# ASD2413.net
KiCad netlist of a schematic drawn in EAGLE
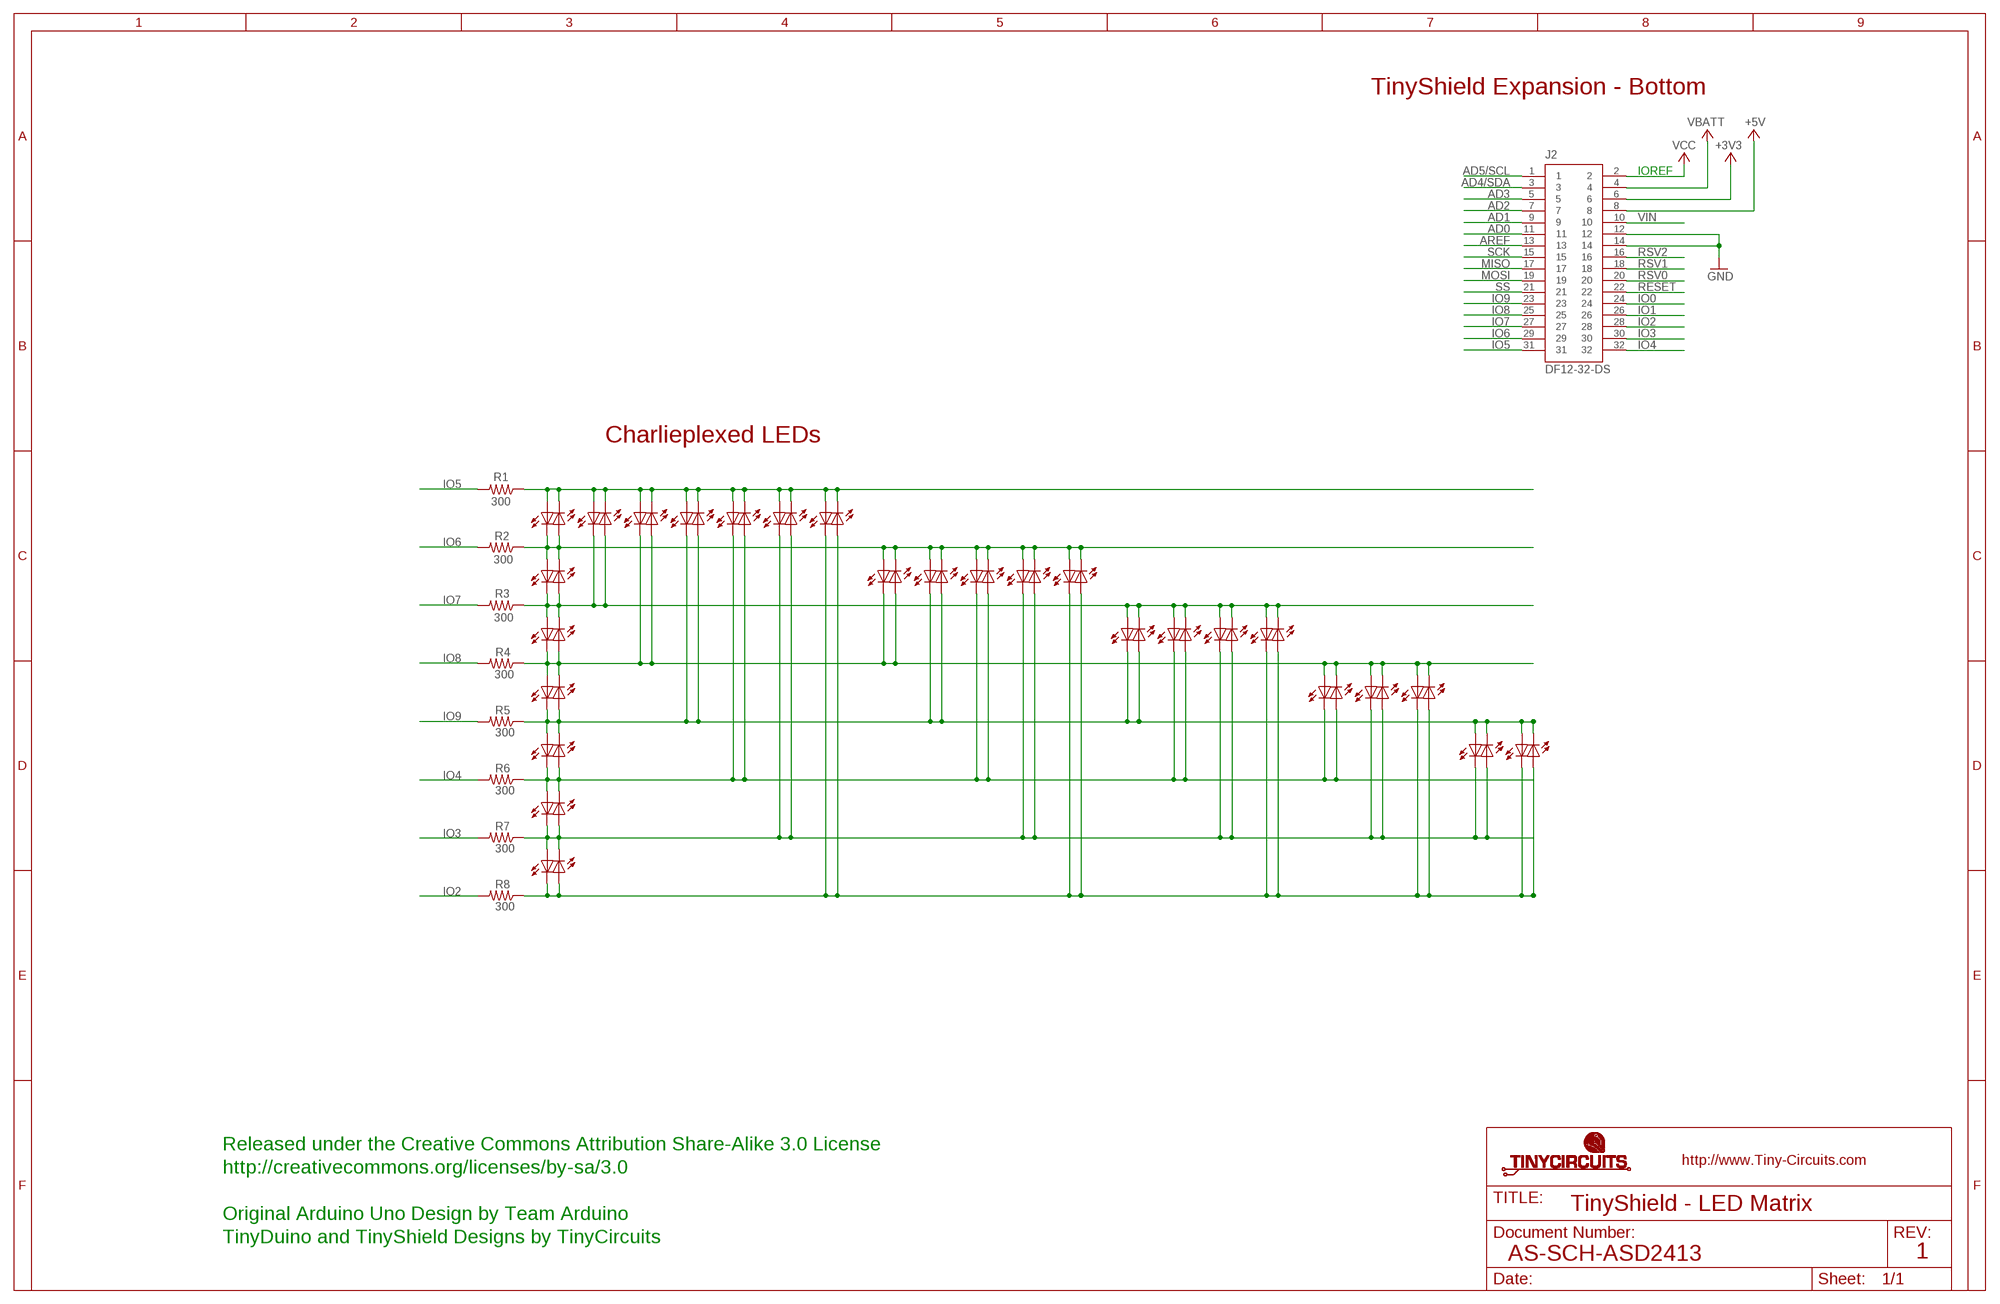
[diagram p0: schematic, sheet 1]

(export (version "E")
  (design (tool "Eeschema 10.0.6"))
  (components
    (comp (ref "D17")
      (value "GREEN")
      (footprint "eagle-import:0402_LED")
      (fields (field (name "PARTNO") "AS-ITM-00038") (field (name "PARTNO_1") "AS-ITM-00038"))
      (libsource (lib "eagle-import") (part "AS-ITM-00038"))
    )
    (comp (ref "D18")
      (value "GREEN")
      (footprint "eagle-import:0402_LED")
      (fields (field (name "PARTNO") "AS-ITM-00038") (field (name "PARTNO_1") "AS-ITM-00038"))
      (libsource (lib "eagle-import") (part "AS-ITM-00038"))
    )
    (comp (ref "D19")
      (value "GREEN")
      (footprint "eagle-import:0402_LED")
      (fields (field (name "PARTNO") "AS-ITM-00038") (field (name "PARTNO_1") "AS-ITM-00038"))
      (libsource (lib "eagle-import") (part "AS-ITM-00038"))
    )
    (comp (ref "D20")
      (value "GREEN")
      (footprint "eagle-import:0402_LED")
      (fields (field (name "PARTNO") "AS-ITM-00038") (field (name "PARTNO_1") "AS-ITM-00038"))
      (libsource (lib "eagle-import") (part "AS-ITM-00038"))
    )
    (comp (ref "D21")
      (value "GREEN")
      (footprint "eagle-import:0402_LED")
      (fields (field (name "PARTNO") "AS-ITM-00038") (field (name "PARTNO_1") "AS-ITM-00038"))
      (libsource (lib "eagle-import") (part "AS-ITM-00038"))
    )
    (comp (ref "D22")
      (value "GREEN")
      (footprint "eagle-import:0402_LED")
      (fields (field (name "PARTNO") "AS-ITM-00038") (field (name "PARTNO_1") "AS-ITM-00038"))
      (libsource (lib "eagle-import") (part "AS-ITM-00038"))
    )
    (comp (ref "D53")
      (value "GREEN")
      (footprint "eagle-import:0402_LED")
      (fields (field (name "PARTNO") "AS-ITM-00038") (field (name "PARTNO_1") "AS-ITM-00038"))
      (libsource (lib "eagle-import") (part "AS-ITM-00038"))
    )
    (comp (ref "D54")
      (value "GREEN")
      (footprint "eagle-import:0402_LED")
      (fields (field (name "PARTNO") "AS-ITM-00038") (field (name "PARTNO_1") "AS-ITM-00038"))
      (libsource (lib "eagle-import") (part "AS-ITM-00038"))
    )
    (comp (ref "D55")
      (value "GREEN")
      (footprint "eagle-import:0402_LED")
      (fields (field (name "PARTNO") "AS-ITM-00038") (field (name "PARTNO_1") "AS-ITM-00038"))
      (libsource (lib "eagle-import") (part "AS-ITM-00038"))
    )
    (comp (ref "D56")
      (value "GREEN")
      (footprint "eagle-import:0402_LED")
      (fields (field (name "PARTNO") "AS-ITM-00038") (field (name "PARTNO_1") "AS-ITM-00038"))
      (libsource (lib "eagle-import") (part "AS-ITM-00038"))
    )
    (comp (ref "D57")
      (value "GREEN")
      (footprint "eagle-import:0402_LED")
      (fields (field (name "PARTNO") "AS-ITM-00038") (field (name "PARTNO_1") "AS-ITM-00038"))
      (libsource (lib "eagle-import") (part "AS-ITM-00038"))
    )
    (comp (ref "D58")
      (value "GREEN")
      (footprint "eagle-import:0402_LED")
      (fields (field (name "PARTNO") "AS-ITM-00038") (field (name "PARTNO_1") "AS-ITM-00038"))
      (libsource (lib "eagle-import") (part "AS-ITM-00038"))
    )
    (comp (ref "D59")
      (value "GREEN")
      (footprint "eagle-import:0402_LED")
      (fields (field (name "PARTNO") "AS-ITM-00038") (field (name "PARTNO_1") "AS-ITM-00038"))
      (libsource (lib "eagle-import") (part "AS-ITM-00038"))
    )
    (comp (ref "D60")
      (value "GREEN")
      (footprint "eagle-import:0402_LED")
      (fields (field (name "PARTNO") "AS-ITM-00038") (field (name "PARTNO_1") "AS-ITM-00038"))
      (libsource (lib "eagle-import") (part "AS-ITM-00038"))
    )
    (comp (ref "D61")
      (value "GREEN")
      (footprint "eagle-import:0402_LED")
      (fields (field (name "PARTNO") "AS-ITM-00038") (field (name "PARTNO_1") "AS-ITM-00038"))
      (libsource (lib "eagle-import") (part "AS-ITM-00038"))
    )
    (comp (ref "D62")
      (value "GREEN")
      (footprint "eagle-import:0402_LED")
      (fields (field (name "PARTNO") "AS-ITM-00038") (field (name "PARTNO_1") "AS-ITM-00038"))
      (libsource (lib "eagle-import") (part "AS-ITM-00038"))
    )
    (comp (ref "D63")
      (value "GREEN")
      (footprint "eagle-import:0402_LED")
      (fields (field (name "PARTNO") "AS-ITM-00038") (field (name "PARTNO_1") "AS-ITM-00038"))
      (libsource (lib "eagle-import") (part "AS-ITM-00038"))
    )
    (comp (ref "D64")
      (value "GREEN")
      (footprint "eagle-import:0402_LED")
      (fields (field (name "PARTNO") "AS-ITM-00038") (field (name "PARTNO_1") "AS-ITM-00038"))
      (libsource (lib "eagle-import") (part "AS-ITM-00038"))
    )
    (comp (ref "D65")
      (value "GREEN")
      (footprint "eagle-import:0402_LED")
      (fields (field (name "PARTNO") "AS-ITM-00038") (field (name "PARTNO_1") "AS-ITM-00038"))
      (libsource (lib "eagle-import") (part "AS-ITM-00038"))
    )
    (comp (ref "D66")
      (value "GREEN")
      (footprint "eagle-import:0402_LED")
      (fields (field (name "PARTNO") "AS-ITM-00038") (field (name "PARTNO_1") "AS-ITM-00038"))
      (libsource (lib "eagle-import") (part "AS-ITM-00038"))
    )
    (comp (ref "D67")
      (value "GREEN")
      (footprint "eagle-import:0402_LED")
      (fields (field (name "PARTNO") "AS-ITM-00038") (field (name "PARTNO_1") "AS-ITM-00038"))
      (libsource (lib "eagle-import") (part "AS-ITM-00038"))
    )
    (comp (ref "D68")
      (value "GREEN")
      (footprint "eagle-import:0402_LED")
      (fields (field (name "PARTNO") "AS-ITM-00038") (field (name "PARTNO_1") "AS-ITM-00038"))
      (libsource (lib "eagle-import") (part "AS-ITM-00038"))
    )
    (comp (ref "D69")
      (value "GREEN")
      (footprint "eagle-import:0402_LED")
      (fields (field (name "PARTNO") "AS-ITM-00038") (field (name "PARTNO_1") "AS-ITM-00038"))
      (libsource (lib "eagle-import") (part "AS-ITM-00038"))
    )
    (comp (ref "D70")
      (value "GREEN")
      (footprint "eagle-import:0402_LED")
      (fields (field (name "PARTNO") "AS-ITM-00038") (field (name "PARTNO_1") "AS-ITM-00038"))
      (libsource (lib "eagle-import") (part "AS-ITM-00038"))
    )
    (comp (ref "D71")
      (value "GREEN")
      (footprint "eagle-import:0402_LED")
      (fields (field (name "PARTNO") "AS-ITM-00038") (field (name "PARTNO_1") "AS-ITM-00038"))
      (libsource (lib "eagle-import") (part "AS-ITM-00038"))
    )
    (comp (ref "D72")
      (value "GREEN")
      (footprint "eagle-import:0402_LED")
      (fields (field (name "PARTNO") "AS-ITM-00038") (field (name "PARTNO_1") "AS-ITM-00038"))
      (libsource (lib "eagle-import") (part "AS-ITM-00038"))
    )
    (comp (ref "D73")
      (value "GREEN")
      (footprint "eagle-import:0402_LED")
      (fields (field (name "PARTNO") "AS-ITM-00038") (field (name "PARTNO_1") "AS-ITM-00038"))
      (libsource (lib "eagle-import") (part "AS-ITM-00038"))
    )
    (comp (ref "D74")
      (value "GREEN")
      (footprint "eagle-import:0402_LED")
      (fields (field (name "PARTNO") "AS-ITM-00038") (field (name "PARTNO_1") "AS-ITM-00038"))
      (libsource (lib "eagle-import") (part "AS-ITM-00038"))
    )
    (comp (ref "D75")
      (value "GREEN")
      (footprint "eagle-import:0402_LED")
      (fields (field (name "PARTNO") "AS-ITM-00038") (field (name "PARTNO_1") "AS-ITM-00038"))
      (libsource (lib "eagle-import") (part "AS-ITM-00038"))
    )
    (comp (ref "D76")
      (value "GREEN")
      (footprint "eagle-import:0402_LED")
      (fields (field (name "PARTNO") "AS-ITM-00038") (field (name "PARTNO_1") "AS-ITM-00038"))
      (libsource (lib "eagle-import") (part "AS-ITM-00038"))
    )
    (comp (ref "D77")
      (value "GREEN")
      (footprint "eagle-import:0402_LED")
      (fields (field (name "PARTNO") "AS-ITM-00038") (field (name "PARTNO_1") "AS-ITM-00038"))
      (libsource (lib "eagle-import") (part "AS-ITM-00038"))
    )
    (comp (ref "D78")
      (value "GREEN")
      (footprint "eagle-import:0402_LED")
      (fields (field (name "PARTNO") "AS-ITM-00038") (field (name "PARTNO_1") "AS-ITM-00038"))
      (libsource (lib "eagle-import") (part "AS-ITM-00038"))
    )
    (comp (ref "D79")
      (value "GREEN")
      (footprint "eagle-import:0402_LED")
      (fields (field (name "PARTNO") "AS-ITM-00038") (field (name "PARTNO_1") "AS-ITM-00038"))
      (libsource (lib "eagle-import") (part "AS-ITM-00038"))
    )
    (comp (ref "D80")
      (value "GREEN")
      (footprint "eagle-import:0402_LED")
      (fields (field (name "PARTNO") "AS-ITM-00038") (field (name "PARTNO_1") "AS-ITM-00038"))
      (libsource (lib "eagle-import") (part "AS-ITM-00038"))
    )
    (comp (ref "D81")
      (value "GREEN")
      (footprint "eagle-import:0402_LED")
      (fields (field (name "PARTNO") "AS-ITM-00038") (field (name "PARTNO_1") "AS-ITM-00038"))
      (libsource (lib "eagle-import") (part "AS-ITM-00038"))
    )
    (comp (ref "D82")
      (value "GREEN")
      (footprint "eagle-import:0402_LED")
      (fields (field (name "PARTNO") "AS-ITM-00038") (field (name "PARTNO_1") "AS-ITM-00038"))
      (libsource (lib "eagle-import") (part "AS-ITM-00038"))
    )
    (comp (ref "D83")
      (value "GREEN")
      (footprint "eagle-import:0402_LED")
      (fields (field (name "PARTNO") "AS-ITM-00038") (field (name "PARTNO_1") "AS-ITM-00038"))
      (libsource (lib "eagle-import") (part "AS-ITM-00038"))
    )
    (comp (ref "D84")
      (value "GREEN")
      (footprint "eagle-import:0402_LED")
      (fields (field (name "PARTNO") "AS-ITM-00038") (field (name "PARTNO_1") "AS-ITM-00038"))
      (libsource (lib "eagle-import") (part "AS-ITM-00038"))
    )
    (comp (ref "D85")
      (value "GREEN")
      (footprint "eagle-import:0402_LED")
      (fields (field (name "PARTNO") "AS-ITM-00038") (field (name "PARTNO_1") "AS-ITM-00038"))
      (libsource (lib "eagle-import") (part "AS-ITM-00038"))
    )
    (comp (ref "D86")
      (value "GREEN")
      (footprint "eagle-import:0402_LED")
      (fields (field (name "PARTNO") "AS-ITM-00038") (field (name "PARTNO_1") "AS-ITM-00038"))
      (libsource (lib "eagle-import") (part "AS-ITM-00038"))
    )
    (comp (ref "D87")
      (value "GREEN")
      (footprint "eagle-import:0402_LED")
      (fields (field (name "PARTNO") "AS-ITM-00038") (field (name "PARTNO_1") "AS-ITM-00038"))
      (libsource (lib "eagle-import") (part "AS-ITM-00038"))
    )
    (comp (ref "D88")
      (value "GREEN")
      (footprint "eagle-import:0402_LED")
      (fields (field (name "PARTNO") "AS-ITM-00038") (field (name "PARTNO_1") "AS-ITM-00038"))
      (libsource (lib "eagle-import") (part "AS-ITM-00038"))
    )
    (comp (ref "D89")
      (value "GREEN")
      (footprint "eagle-import:0402_LED")
      (fields (field (name "PARTNO") "AS-ITM-00038") (field (name "PARTNO_1") "AS-ITM-00038"))
      (libsource (lib "eagle-import") (part "AS-ITM-00038"))
    )
    (comp (ref "D90")
      (value "GREEN")
      (footprint "eagle-import:0402_LED")
      (fields (field (name "PARTNO") "AS-ITM-00038") (field (name "PARTNO_1") "AS-ITM-00038"))
      (libsource (lib "eagle-import") (part "AS-ITM-00038"))
    )
    (comp (ref "D91")
      (value "GREEN")
      (footprint "eagle-import:0402_LED")
      (fields (field (name "PARTNO") "AS-ITM-00038") (field (name "PARTNO_1") "AS-ITM-00038"))
      (libsource (lib "eagle-import") (part "AS-ITM-00038"))
    )
    (comp (ref "D92")
      (value "GREEN")
      (footprint "eagle-import:0402_LED")
      (fields (field (name "PARTNO") "AS-ITM-00038") (field (name "PARTNO_1") "AS-ITM-00038"))
      (libsource (lib "eagle-import") (part "AS-ITM-00038"))
    )
    (comp (ref "D93")
      (value "GREEN")
      (footprint "eagle-import:0402_LED")
      (fields (field (name "PARTNO") "AS-ITM-00038") (field (name "PARTNO_1") "AS-ITM-00038"))
      (libsource (lib "eagle-import") (part "AS-ITM-00038"))
    )
    (comp (ref "D94")
      (value "GREEN")
      (footprint "eagle-import:0402_LED")
      (fields (field (name "PARTNO") "AS-ITM-00038") (field (name "PARTNO_1") "AS-ITM-00038"))
      (libsource (lib "eagle-import") (part "AS-ITM-00038"))
    )
    (comp (ref "D95")
      (value "GREEN")
      (footprint "eagle-import:0402_LED")
      (fields (field (name "PARTNO") "AS-ITM-00038") (field (name "PARTNO_1") "AS-ITM-00038"))
      (libsource (lib "eagle-import") (part "AS-ITM-00038"))
    )
    (comp (ref "D96")
      (value "GREEN")
      (footprint "eagle-import:0402_LED")
      (fields (field (name "PARTNO") "AS-ITM-00038") (field (name "PARTNO_1") "AS-ITM-00038"))
      (libsource (lib "eagle-import") (part "AS-ITM-00038"))
    )
    (comp (ref "D97")
      (value "GREEN")
      (footprint "eagle-import:0402_LED")
      (fields (field (name "PARTNO") "AS-ITM-00038") (field (name "PARTNO_1") "AS-ITM-00038"))
      (libsource (lib "eagle-import") (part "AS-ITM-00038"))
    )
    (comp (ref "D98")
      (value "GREEN")
      (footprint "eagle-import:0402_LED")
      (fields (field (name "PARTNO") "AS-ITM-00038") (field (name "PARTNO_1") "AS-ITM-00038"))
      (libsource (lib "eagle-import") (part "AS-ITM-00038"))
    )
    (comp (ref "D99")
      (value "GREEN")
      (footprint "eagle-import:0402_LED")
      (fields (field (name "PARTNO") "AS-ITM-00038") (field (name "PARTNO_1") "AS-ITM-00038"))
      (libsource (lib "eagle-import") (part "AS-ITM-00038"))
    )
    (comp (ref "D100")
      (value "GREEN")
      (footprint "eagle-import:0402_LED")
      (fields (field (name "PARTNO") "AS-ITM-00038") (field (name "PARTNO_1") "AS-ITM-00038"))
      (libsource (lib "eagle-import") (part "AS-ITM-00038"))
    )
    (comp (ref "J2")
      (value "DF12-32-DS")
      (footprint "eagle-import:DF12-32-DS")
      (fields (field (name "PARTNO") "AS-ITM-00012") (field (name "PARTNO_1") "AS-ITM-00012"))
      (libsource (lib "eagle-import") (part "AS-ITM-00012"))
    )
    (comp (ref "R1")
      (value "300")
      (footprint "eagle-import:0402")
      (fields (field (name "PARTNO") "AS-ITM-00016") (field (name "PARTNO_1") "AS-ITM-00016"))
      (libsource (lib "eagle-import") (part "AS-ITM-00016"))
    )
    (comp (ref "R2")
      (value "300")
      (footprint "eagle-import:0402")
      (fields (field (name "PARTNO") "AS-ITM-00016"))
      (libsource (lib "eagle-import") (part "AS-ITM-00016"))
    )
    (comp (ref "R3")
      (value "300")
      (footprint "eagle-import:0402")
      (fields (field (name "PARTNO") "AS-ITM-00016"))
      (libsource (lib "eagle-import") (part "AS-ITM-00016"))
    )
    (comp (ref "R4")
      (value "300")
      (footprint "eagle-import:0402")
      (fields (field (name "PARTNO") "AS-ITM-00016"))
      (libsource (lib "eagle-import") (part "AS-ITM-00016"))
    )
    (comp (ref "R5")
      (value "300")
      (footprint "eagle-import:0402")
      (fields (field (name "PARTNO") "AS-ITM-00016"))
      (libsource (lib "eagle-import") (part "AS-ITM-00016"))
    )
    (comp (ref "R6")
      (value "300")
      (footprint "eagle-import:0402")
      (fields (field (name "PARTNO") "AS-ITM-00016") (field (name "PARTNO_1") "AS-ITM-00016"))
      (libsource (lib "eagle-import") (part "AS-ITM-00016"))
    )
    (comp (ref "R7")
      (value "300")
      (footprint "eagle-import:0402")
      (fields (field (name "PARTNO") "AS-ITM-00016") (field (name "PARTNO_1") "AS-ITM-00016"))
      (libsource (lib "eagle-import") (part "AS-ITM-00016"))
    )
    (comp (ref "R8")
      (value "300")
      (footprint "eagle-import:0402")
      (fields (field (name "PARTNO") "AS-ITM-00016") (field (name "PARTNO_1") "AS-ITM-00016"))
      (libsource (lib "eagle-import") (part "AS-ITM-00016"))
    )
  )
  (nets
    (net (code "1") (name "+3V3") (class "Default")
      (node (ref "J2") (pin "6") (pinfunction "6_6") (pintype "bidirectional"))
    )
    (net (code "2") (name "+5V") (class "Default")
      (node (ref "J2") (pin "8") (pinfunction "8_8") (pintype "bidirectional"))
    )
    (net (code "3") (name "/AD0") (class "Default")
      (node (ref "J2") (pin "11") (pinfunction "11_11") (pintype "bidirectional"))
    )
    (net (code "4") (name "/AD1") (class "Default")
      (node (ref "J2") (pin "9") (pinfunction "9_9") (pintype "bidirectional"))
    )
    (net (code "5") (name "/AD2") (class "Default")
      (node (ref "J2") (pin "7") (pinfunction "7_7") (pintype "bidirectional"))
    )
    (net (code "6") (name "/AD3") (class "Default")
      (node (ref "J2") (pin "5") (pinfunction "5_5") (pintype "bidirectional"))
    )
    (net (code "7") (name "/AD4{slash}SDA") (class "Default")
      (node (ref "J2") (pin "3") (pinfunction "3_3") (pintype "bidirectional"))
    )
    (net (code "8") (name "/AD5{slash}SCL") (class "Default")
      (node (ref "J2") (pin "1") (pinfunction "1_1") (pintype "bidirectional"))
    )
    (net (code "9") (name "/AREF") (class "Default")
      (node (ref "J2") (pin "13") (pinfunction "13_13") (pintype "bidirectional"))
    )
    (net (code "10") (name "/IO0") (class "Default")
      (node (ref "J2") (pin "24") (pinfunction "24_24") (pintype "bidirectional"))
    )
    (net (code "11") (name "/IO1") (class "Default")
      (node (ref "J2") (pin "26") (pinfunction "26_26") (pintype "bidirectional"))
    )
    (net (code "12") (name "/IO2") (class "Default")
      (node (ref "J2") (pin "28") (pinfunction "28_28") (pintype "bidirectional"))
      (node (ref "R8") (pin "2") (pinfunction "2_2") (pintype "passive"))
    )
    (net (code "13") (name "/IO3") (class "Default")
      (node (ref "J2") (pin "30") (pinfunction "30_30") (pintype "bidirectional"))
      (node (ref "R7") (pin "2") (pinfunction "2_2") (pintype "passive"))
    )
    (net (code "14") (name "/IO4") (class "Default")
      (node (ref "J2") (pin "32") (pinfunction "32_32") (pintype "bidirectional"))
      (node (ref "R6") (pin "2") (pinfunction "2_2") (pintype "passive"))
    )
    (net (code "15") (name "/IO5") (class "Default")
      (node (ref "J2") (pin "31") (pinfunction "31_31") (pintype "bidirectional"))
      (node (ref "R1") (pin "2") (pinfunction "2_2") (pintype "passive"))
    )
    (net (code "16") (name "/IO6") (class "Default")
      (node (ref "J2") (pin "29") (pinfunction "29_29") (pintype "bidirectional"))
      (node (ref "R2") (pin "2") (pinfunction "2_2") (pintype "passive"))
    )
    (net (code "17") (name "/IO7") (class "Default")
      (node (ref "J2") (pin "27") (pinfunction "27_27") (pintype "bidirectional"))
      (node (ref "R3") (pin "2") (pinfunction "2_2") (pintype "passive"))
    )
    (net (code "18") (name "/IO8") (class "Default")
      (node (ref "J2") (pin "25") (pinfunction "25_25") (pintype "bidirectional"))
      (node (ref "R4") (pin "2") (pinfunction "2_2") (pintype "passive"))
    )
    (net (code "19") (name "/IO9") (class "Default")
      (node (ref "J2") (pin "23") (pinfunction "23_23") (pintype "bidirectional"))
      (node (ref "R5") (pin "2") (pinfunction "2_2") (pintype "passive"))
    )
    (net (code "20") (name "/MISO") (class "Default")
      (node (ref "J2") (pin "17") (pinfunction "17_17") (pintype "bidirectional"))
    )
    (net (code "21") (name "/MOSI") (class "Default")
      (node (ref "J2") (pin "19") (pinfunction "19_19") (pintype "bidirectional"))
    )
    (net (code "22") (name "/RESET") (class "Default")
      (node (ref "J2") (pin "22") (pinfunction "22_22") (pintype "bidirectional"))
    )
    (net (code "23") (name "/RSV0") (class "Default")
      (node (ref "J2") (pin "20") (pinfunction "20_20") (pintype "bidirectional"))
    )
    (net (code "24") (name "/RSV1") (class "Default")
      (node (ref "J2") (pin "18") (pinfunction "18_18") (pintype "bidirectional"))
    )
    (net (code "25") (name "/RSV2") (class "Default")
      (node (ref "J2") (pin "16") (pinfunction "16_16") (pintype "bidirectional"))
    )
    (net (code "26") (name "/SCK") (class "Default")
      (node (ref "J2") (pin "15") (pinfunction "15_15") (pintype "bidirectional"))
    )
    (net (code "27") (name "/SS") (class "Default")
      (node (ref "J2") (pin "21") (pinfunction "21_21") (pintype "bidirectional"))
    )
    (net (code "28") (name "/VIN") (class "Default")
      (node (ref "J2") (pin "10") (pinfunction "10_10") (pintype "bidirectional"))
    )
    (net (code "29") (name "GND") (class "Default")
      (node (ref "J2") (pin "12") (pinfunction "12_12") (pintype "bidirectional"))
      (node (ref "J2") (pin "14") (pinfunction "14_14") (pintype "bidirectional"))
    )
    (net (code "30") (name "Net-(D17-A)") (class "Default")
      (node (ref "D17") (pin "1") (pinfunction "A_1") (pintype "passive"))
      (node (ref "D18") (pin "2") (pinfunction "C_2") (pintype "passive"))
      (node (ref "D19") (pin "1") (pinfunction "A_1") (pintype "passive"))
      (node (ref "D20") (pin "2") (pinfunction "C_2") (pintype "passive"))
      (node (ref "D21") (pin "1") (pinfunction "A_1") (pintype "passive"))
      (node (ref "D22") (pin "2") (pinfunction "C_2") (pintype "passive"))
      (node (ref "D53") (pin "1") (pinfunction "A_1") (pintype "passive"))
      (node (ref "D54") (pin "2") (pinfunction "C_2") (pintype "passive"))
      (node (ref "D55") (pin "1") (pinfunction "A_1") (pintype "passive"))
      (node (ref "D56") (pin "2") (pinfunction "C_2") (pintype "passive"))
      (node (ref "D57") (pin "1") (pinfunction "A_1") (pintype "passive"))
      (node (ref "D58") (pin "2") (pinfunction "C_2") (pintype "passive"))
      (node (ref "D59") (pin "1") (pinfunction "A_1") (pintype "passive"))
      (node (ref "D60") (pin "2") (pinfunction "C_2") (pintype "passive"))
      (node (ref "R1") (pin "1") (pinfunction "1_1") (pintype "passive"))
    )
    (net (code "31") (name "Net-(D17-C)") (class "Default")
      (node (ref "D17") (pin "2") (pinfunction "C_2") (pintype "passive"))
      (node (ref "D18") (pin "1") (pinfunction "A_1") (pintype "passive"))
      (node (ref "D61") (pin "1") (pinfunction "A_1") (pintype "passive"))
      (node (ref "D62") (pin "2") (pinfunction "C_2") (pintype "passive"))
      (node (ref "D63") (pin "1") (pinfunction "A_1") (pintype "passive"))
      (node (ref "D64") (pin "2") (pinfunction "C_2") (pintype "passive"))
      (node (ref "D65") (pin "1") (pinfunction "A_1") (pintype "passive"))
      (node (ref "D66") (pin "2") (pinfunction "C_2") (pintype "passive"))
      (node (ref "D67") (pin "1") (pinfunction "A_1") (pintype "passive"))
      (node (ref "D68") (pin "2") (pinfunction "C_2") (pintype "passive"))
      (node (ref "D69") (pin "1") (pinfunction "A_1") (pintype "passive"))
      (node (ref "D70") (pin "2") (pinfunction "C_2") (pintype "passive"))
      (node (ref "D85") (pin "1") (pinfunction "A_1") (pintype "passive"))
      (node (ref "D86") (pin "2") (pinfunction "C_2") (pintype "passive"))
      (node (ref "R2") (pin "1") (pinfunction "1_1") (pintype "passive"))
    )
    (net (code "32") (name "Net-(D19-C)") (class "Default")
      (node (ref "D19") (pin "2") (pinfunction "C_2") (pintype "passive"))
      (node (ref "D20") (pin "1") (pinfunction "A_1") (pintype "passive"))
      (node (ref "D61") (pin "2") (pinfunction "C_2") (pintype "passive"))
      (node (ref "D62") (pin "1") (pinfunction "A_1") (pintype "passive"))
      (node (ref "D71") (pin "1") (pinfunction "A_1") (pintype "passive"))
      (node (ref "D72") (pin "2") (pinfunction "C_2") (pintype "passive"))
      (node (ref "D73") (pin "1") (pinfunction "A_1") (pintype "passive"))
      (node (ref "D74") (pin "2") (pinfunction "C_2") (pintype "passive"))
      (node (ref "D83") (pin "1") (pinfunction "A_1") (pintype "passive"))
      (node (ref "D84") (pin "2") (pinfunction "C_2") (pintype "passive"))
      (node (ref "D87") (pin "1") (pinfunction "A_1") (pintype "passive"))
      (node (ref "D88") (pin "2") (pinfunction "C_2") (pintype "passive"))
      (node (ref "D89") (pin "1") (pinfunction "A_1") (pintype "passive"))
      (node (ref "D90") (pin "2") (pinfunction "C_2") (pintype "passive"))
      (node (ref "R3") (pin "1") (pinfunction "1_1") (pintype "passive"))
    )
    (net (code "33") (name "Net-(D21-C)") (class "Default")
      (node (ref "D21") (pin "2") (pinfunction "C_2") (pintype "passive"))
      (node (ref "D22") (pin "1") (pinfunction "A_1") (pintype "passive"))
      (node (ref "D73") (pin "2") (pinfunction "C_2") (pintype "passive"))
      (node (ref "D74") (pin "1") (pinfunction "A_1") (pintype "passive"))
      (node (ref "D75") (pin "1") (pinfunction "A_1") (pintype "passive"))
      (node (ref "D76") (pin "2") (pinfunction "C_2") (pintype "passive"))
      (node (ref "D85") (pin "2") (pinfunction "C_2") (pintype "passive"))
      (node (ref "D86") (pin "1") (pinfunction "A_1") (pintype "passive"))
      (node (ref "D91") (pin "1") (pinfunction "A_1") (pintype "passive"))
      (node (ref "D92") (pin "2") (pinfunction "C_2") (pintype "passive"))
      (node (ref "D93") (pin "1") (pinfunction "A_1") (pintype "passive"))
      (node (ref "D94") (pin "2") (pinfunction "C_2") (pintype "passive"))
      (node (ref "D95") (pin "1") (pinfunction "A_1") (pintype "passive"))
      (node (ref "D96") (pin "2") (pinfunction "C_2") (pintype "passive"))
      (node (ref "R4") (pin "1") (pinfunction "1_1") (pintype "passive"))
    )
    (net (code "34") (name "Net-(D55-C)") (class "Default")
      (node (ref "D55") (pin "2") (pinfunction "C_2") (pintype "passive"))
      (node (ref "D56") (pin "1") (pinfunction "A_1") (pintype "passive"))
      (node (ref "D65") (pin "2") (pinfunction "C_2") (pintype "passive"))
      (node (ref "D66") (pin "1") (pinfunction "A_1") (pintype "passive"))
      (node (ref "D77") (pin "2") (pinfunction "C_2") (pintype "passive"))
      (node (ref "D78") (pin "1") (pinfunction "A_1") (pintype "passive"))
      (node (ref "D79") (pin "1") (pinfunction "A_1") (pintype "passive"))
      (node (ref "D80") (pin "2") (pinfunction "C_2") (pintype "passive"))
      (node (ref "D83") (pin "2") (pinfunction "C_2") (pintype "passive"))
      (node (ref "D84") (pin "1") (pinfunction "A_1") (pintype "passive"))
      (node (ref "D91") (pin "2") (pinfunction "C_2") (pintype "passive"))
      (node (ref "D92") (pin "1") (pinfunction "A_1") (pintype "passive"))
      (node (ref "R6") (pin "1") (pinfunction "1_1") (pintype "passive"))
    )
    (net (code "35") (name "Net-(D57-C)") (class "Default")
      (node (ref "D57") (pin "2") (pinfunction "C_2") (pintype "passive"))
      (node (ref "D58") (pin "1") (pinfunction "A_1") (pintype "passive"))
      (node (ref "D67") (pin "2") (pinfunction "C_2") (pintype "passive"))
      (node (ref "D68") (pin "1") (pinfunction "A_1") (pintype "passive"))
      (node (ref "D79") (pin "2") (pinfunction "C_2") (pintype "passive"))
      (node (ref "D80") (pin "1") (pinfunction "A_1") (pintype "passive"))
      (node (ref "D81") (pin "1") (pinfunction "A_1") (pintype "passive"))
      (node (ref "D82") (pin "2") (pinfunction "C_2") (pintype "passive"))
      (node (ref "D87") (pin "2") (pinfunction "C_2") (pintype "passive"))
      (node (ref "D88") (pin "1") (pinfunction "A_1") (pintype "passive"))
      (node (ref "D93") (pin "2") (pinfunction "C_2") (pintype "passive"))
      (node (ref "D94") (pin "1") (pinfunction "A_1") (pintype "passive"))
      (node (ref "D97") (pin "2") (pinfunction "C_2") (pintype "passive"))
      (node (ref "D98") (pin "1") (pinfunction "A_1") (pintype "passive"))
      (node (ref "R7") (pin "1") (pinfunction "1_1") (pintype "passive"))
    )
    (net (code "36") (name "Net-(D100-A)") (class "Default")
      (node (ref "D100") (pin "1") (pinfunction "A_1") (pintype "passive"))
      (node (ref "D59") (pin "2") (pinfunction "C_2") (pintype "passive"))
      (node (ref "D60") (pin "1") (pinfunction "A_1") (pintype "passive"))
      (node (ref "D69") (pin "2") (pinfunction "C_2") (pintype "passive"))
      (node (ref "D70") (pin "1") (pinfunction "A_1") (pintype "passive"))
      (node (ref "D81") (pin "2") (pinfunction "C_2") (pintype "passive"))
      (node (ref "D82") (pin "1") (pinfunction "A_1") (pintype "passive"))
      (node (ref "D89") (pin "2") (pinfunction "C_2") (pintype "passive"))
      (node (ref "D90") (pin "1") (pinfunction "A_1") (pintype "passive"))
      (node (ref "D95") (pin "2") (pinfunction "C_2") (pintype "passive"))
      (node (ref "D96") (pin "1") (pinfunction "A_1") (pintype "passive"))
      (node (ref "D99") (pin "2") (pinfunction "C_2") (pintype "passive"))
      (node (ref "R8") (pin "1") (pinfunction "1_1") (pintype "passive"))
    )
    (net (code "37") (name "Net-(D100-C)") (class "Default")
      (node (ref "D100") (pin "2") (pinfunction "C_2") (pintype "passive"))
      (node (ref "D53") (pin "2") (pinfunction "C_2") (pintype "passive"))
      (node (ref "D54") (pin "1") (pinfunction "A_1") (pintype "passive"))
      (node (ref "D63") (pin "2") (pinfunction "C_2") (pintype "passive"))
      (node (ref "D64") (pin "1") (pinfunction "A_1") (pintype "passive"))
      (node (ref "D71") (pin "2") (pinfunction "C_2") (pintype "passive"))
      (node (ref "D72") (pin "1") (pinfunction "A_1") (pintype "passive"))
      (node (ref "D75") (pin "2") (pinfunction "C_2") (pintype "passive"))
      (node (ref "D76") (pin "1") (pinfunction "A_1") (pintype "passive"))
      (node (ref "D77") (pin "1") (pinfunction "A_1") (pintype "passive"))
      (node (ref "D78") (pin "2") (pinfunction "C_2") (pintype "passive"))
      (node (ref "D97") (pin "1") (pinfunction "A_1") (pintype "passive"))
      (node (ref "D98") (pin "2") (pinfunction "C_2") (pintype "passive"))
      (node (ref "D99") (pin "1") (pinfunction "A_1") (pintype "passive"))
      (node (ref "R5") (pin "1") (pinfunction "1_1") (pintype "passive"))
    )
    (net (code "38") (name "VBATT") (class "Default")
      (node (ref "J2") (pin "4") (pinfunction "4_4") (pintype "bidirectional"))
    )
    (net (code "39") (name "VCC") (class "Default")
      (node (ref "J2") (pin "2") (pinfunction "2_2") (pintype "bidirectional"))
    )
  )
)
